# 03_mcu_io.net
KiCad netlist of a schematic drawn in Altium Designer
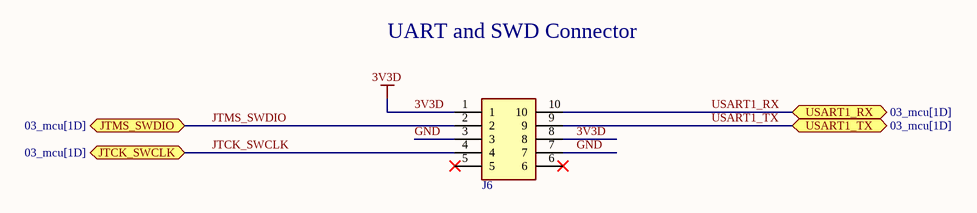
[diagram p0: 03_mcu_io.SchDoc]

(export (version "E")
  (design (tool "Eeschema 10.0.6"))
  (components
    (comp (ref "J6")
      (value "TC2050-IDC")
      (footprint "TAG-CONNECT_TC2050-IDC")
      (description "Cbl Plug-Of-Nails 10-Pin w/Legs")
      (libsource (lib "tcspc00") (part "TC2050-IDC"))
    )
  )
  (nets
    (net (code "1") (name "/GND") (class "Default")
      (node (ref "J6") (pin "3") (pinfunction "3_3") (pintype "passive"))
      (node (ref "J6") (pin "7") (pinfunction "7_7") (pintype "passive"))
    )
    (net (code "2") (name "/JTCK_SWCLK") (class "Default")
      (node (ref "J6") (pin "4") (pinfunction "4_4") (pintype "passive"))
    )
    (net (code "3") (name "/JTMS_SWDIO") (class "Default")
      (node (ref "J6") (pin "2") (pinfunction "2_2") (pintype "passive"))
    )
    (net (code "4") (name "/USART1_RX") (class "Default")
      (node (ref "J6") (pin "10") (pinfunction "10_10") (pintype "passive"))
    )
    (net (code "5") (name "/USART1_TX") (class "Default")
      (node (ref "J6") (pin "9") (pinfunction "9_9") (pintype "passive"))
    )
    (net (code "6") (name "3V3D") (class "Default")
      (node (ref "J6") (pin "1") (pinfunction "1_1") (pintype "passive"))
      (node (ref "J6") (pin "8") (pinfunction "8_8") (pintype "passive"))
    )
    (net (code "7") (name "unconnected-(J6-Pad5)") (class "Default")
      (node (ref "J6") (pin "5") (pinfunction "5_5") (pintype "passive+no_connect"))
    )
    (net (code "8") (name "unconnected-(J6-Pad6)") (class "Default")
      (node (ref "J6") (pin "6") (pinfunction "6_6") (pintype "passive+no_connect"))
    )
  )
)
